# dos-partes.net
KiCad netlist of a schematic drawn in EAGLE
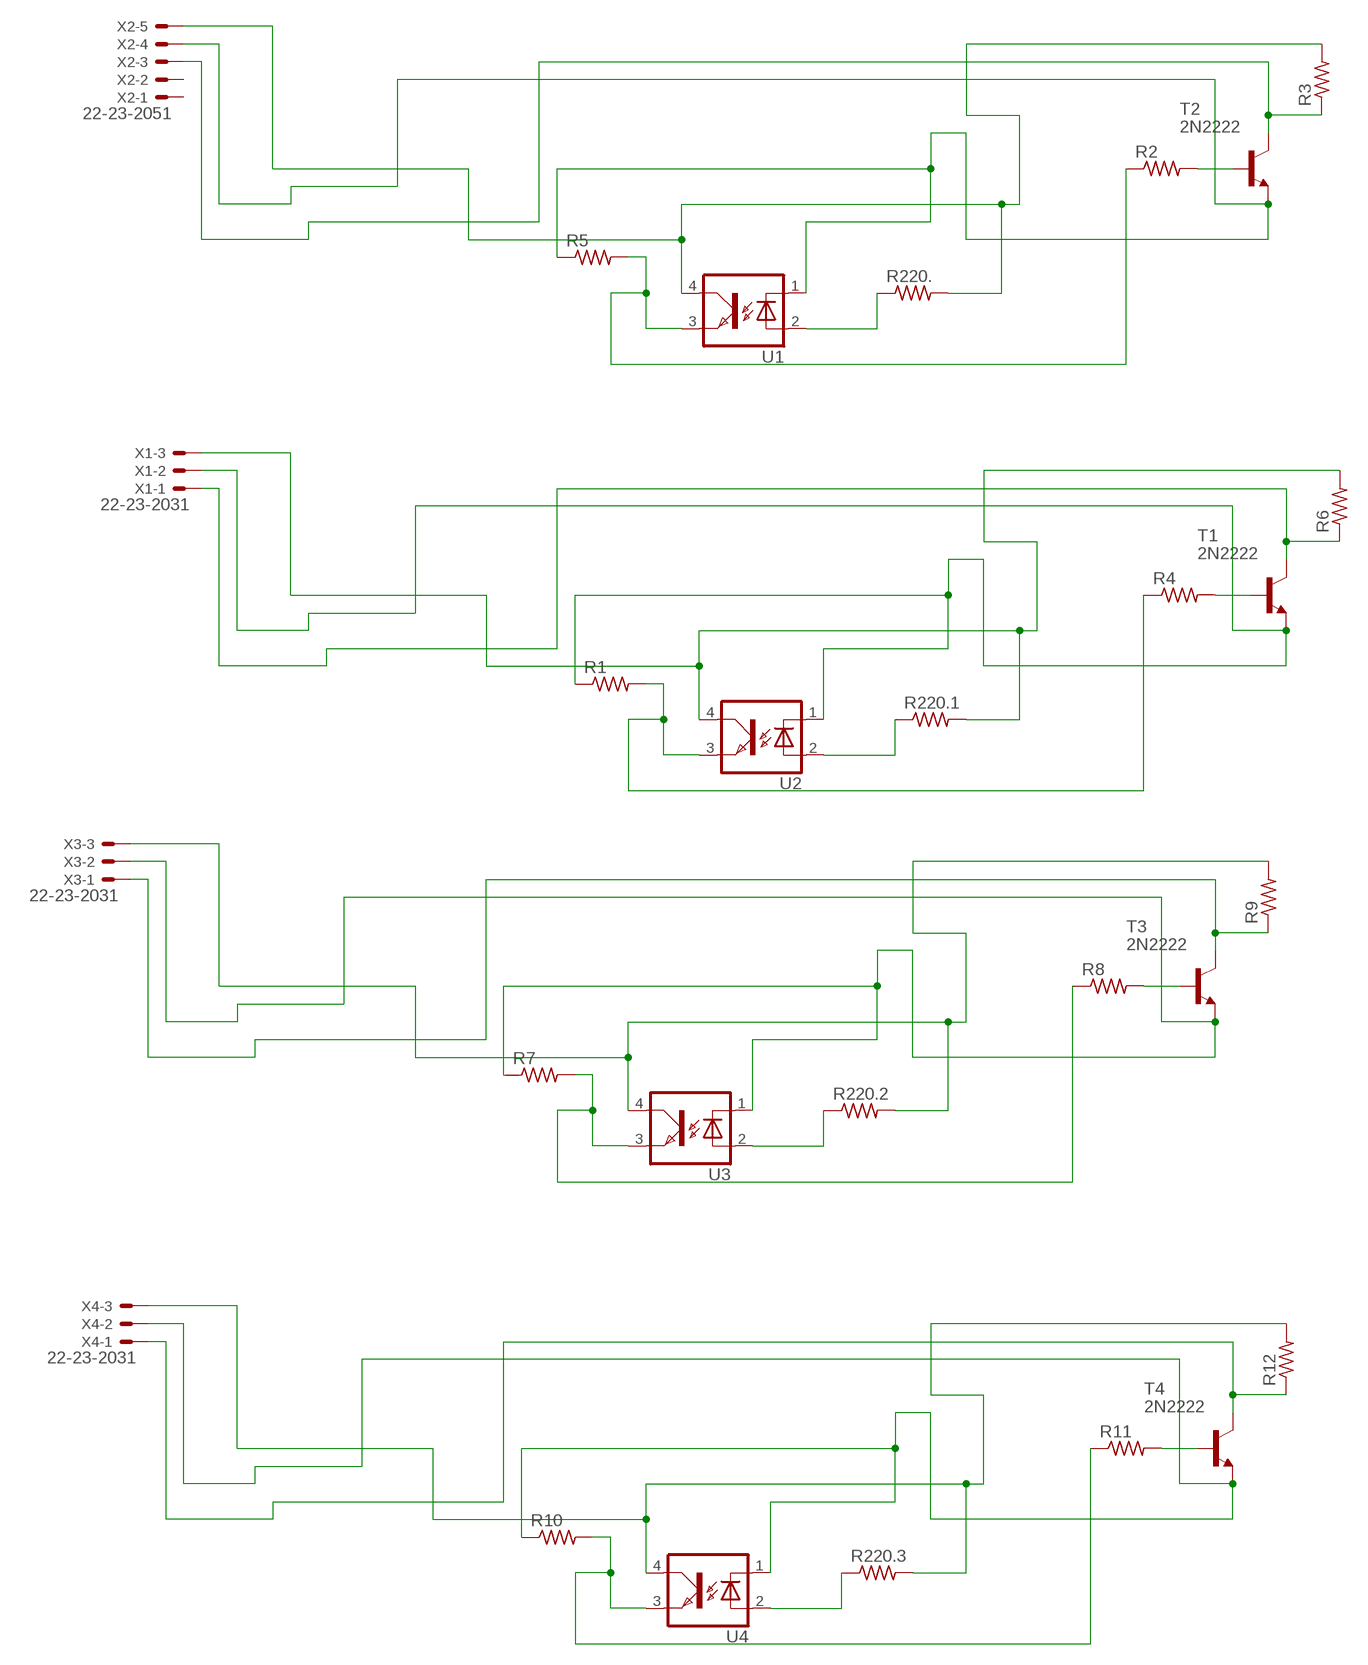
[diagram p0: schematic, sheet 1]

(export (version "E")
  (design (tool "Eeschema 10.0.6"))
  (components
    (comp (ref "R1")
      (value "R-US_0204/7")
      (footprint "eagle-import:0204_7")
      (libsource (lib "eagle-import") (part "R-US_0204/7"))
    )
    (comp (ref "R2")
      (value "R-US_0204/7")
      (footprint "eagle-import:0204_7")
      (libsource (lib "eagle-import") (part "R-US_0204/7"))
    )
    (comp (ref "R3")
      (value "R-US_0204/7")
      (footprint "eagle-import:0204_7")
      (libsource (lib "eagle-import") (part "R-US_0204/7"))
    )
    (comp (ref "R4")
      (value "R-US_0204/7")
      (footprint "eagle-import:0204_7")
      (libsource (lib "eagle-import") (part "R-US_0204/7"))
    )
    (comp (ref "R5")
      (value "R-US_0204/7")
      (footprint "eagle-import:0204_7")
      (libsource (lib "eagle-import") (part "R-US_0204/7"))
    )
    (comp (ref "R6")
      (value "R-US_0204/7")
      (footprint "eagle-import:0204_7")
      (libsource (lib "eagle-import") (part "R-US_0204/7"))
    )
    (comp (ref "R7")
      (value "R-US_0204/7")
      (footprint "eagle-import:0204_7")
      (libsource (lib "eagle-import") (part "R-US_0204/7"))
    )
    (comp (ref "R8")
      (value "R-US_0204/7")
      (footprint "eagle-import:0204_7")
      (libsource (lib "eagle-import") (part "R-US_0204/7"))
    )
    (comp (ref "R9")
      (value "R-US_0204/7")
      (footprint "eagle-import:0204_7")
      (libsource (lib "eagle-import") (part "R-US_0204/7"))
    )
    (comp (ref "R10")
      (value "R-US_0204/7")
      (footprint "eagle-import:0204_7")
      (libsource (lib "eagle-import") (part "R-US_0204/7"))
    )
    (comp (ref "R11")
      (value "R-US_0204/7")
      (footprint "eagle-import:0204_7")
      (libsource (lib "eagle-import") (part "R-US_0204/7"))
    )
    (comp (ref "R12")
      (value "R-US_0204/7")
      (footprint "eagle-import:0204_7")
      (libsource (lib "eagle-import") (part "R-US_0204/7"))
    )
    (comp (ref "R220.")
      (value "R-US_0204/7")
      (footprint "eagle-import:0204_7")
      (libsource (lib "eagle-import") (part "R-US_0204/7"))
    )
    (comp (ref "R220.1")
      (value "R-US_0204/7")
      (footprint "eagle-import:0204_7")
      (libsource (lib "eagle-import") (part "R-US_0204/7"))
    )
    (comp (ref "R220.2")
      (value "R-US_0204/7")
      (footprint "eagle-import:0204_7")
      (libsource (lib "eagle-import") (part "R-US_0204/7"))
    )
    (comp (ref "R220.3")
      (value "R-US_0204/7")
      (footprint "eagle-import:0204_7")
      (libsource (lib "eagle-import") (part "R-US_0204/7"))
    )
    (comp (ref "T1")
      (value "2N2222")
      (footprint "eagle-import:TO18")
      (libsource (lib "eagle-import") (part "2N2222"))
    )
    (comp (ref "T2")
      (value "2N2222")
      (footprint "eagle-import:TO18")
      (libsource (lib "eagle-import") (part "2N2222"))
    )
    (comp (ref "T3")
      (value "2N2222")
      (footprint "eagle-import:TO18")
      (libsource (lib "eagle-import") (part "2N2222"))
    )
    (comp (ref "T4")
      (value "2N2222")
      (footprint "eagle-import:TO18")
      (libsource (lib "eagle-import") (part "2N2222"))
    )
    (comp (ref "U1")
      (value "CNY70")
      (footprint "eagle-import:CNY70")
      (libsource (lib "eagle-import") (part "CNY70"))
    )
    (comp (ref "U2")
      (value "CNY70")
      (footprint "eagle-import:CNY70")
      (libsource (lib "eagle-import") (part "CNY70"))
    )
    (comp (ref "U3")
      (value "CNY70")
      (footprint "eagle-import:CNY70")
      (libsource (lib "eagle-import") (part "CNY70"))
    )
    (comp (ref "U4")
      (value "CNY70")
      (footprint "eagle-import:CNY70")
      (libsource (lib "eagle-import") (part "CNY70"))
    )
    (comp (ref "X1")
      (value "22-23-2031")
      (footprint "eagle-import:22-23-2031")
      (fields (field (name "MF") "MOLEX"))
      (libsource (lib "eagle-import") (part "22-23-2031"))
    )
    (comp (ref "X2")
      (value "22-23-2051")
      (footprint "eagle-import:22-23-2051")
      (fields (field (name "MF") "MOLEX"))
      (libsource (lib "eagle-import") (part "22-23-2051"))
    )
    (comp (ref "X3")
      (value "22-23-2031")
      (footprint "eagle-import:22-23-2031")
      (fields (field (name "MF") "MOLEX"))
      (libsource (lib "eagle-import") (part "22-23-2031"))
    )
    (comp (ref "X4")
      (value "22-23-2031")
      (footprint "eagle-import:22-23-2031")
      (fields (field (name "MF") "MOLEX"))
      (libsource (lib "eagle-import") (part "22-23-2031"))
    )
  )
  (nets
    (net (code "1") (name "Net-(R1-Pad2)") (class "Default")
      (node (ref "R1") (pin "2") (pinfunction "2_2") (pintype "passive"))
      (node (ref "R4") (pin "1") (pinfunction "1_1") (pintype "passive"))
      (node (ref "U2") (pin "3") (pinfunction "3_3") (pintype "passive"))
    )
    (net (code "2") (name "Net-(R2-Pad1)") (class "Default")
      (node (ref "R2") (pin "1") (pinfunction "1_1") (pintype "passive"))
      (node (ref "R5") (pin "2") (pinfunction "2_2") (pintype "passive"))
      (node (ref "U1") (pin "3") (pinfunction "3_3") (pintype "passive"))
    )
    (net (code "3") (name "Net-(R7-Pad2)") (class "Default")
      (node (ref "R7") (pin "2") (pinfunction "2_2") (pintype "passive"))
      (node (ref "R8") (pin "1") (pinfunction "1_1") (pintype "passive"))
      (node (ref "U3") (pin "3") (pinfunction "3_3") (pintype "passive"))
    )
    (net (code "4") (name "Net-(R10-Pad2)") (class "Default")
      (node (ref "R10") (pin "2") (pinfunction "2_2") (pintype "passive"))
      (node (ref "R11") (pin "1") (pinfunction "1_1") (pintype "passive"))
      (node (ref "U4") (pin "3") (pinfunction "3_3") (pintype "passive"))
    )
    (net (code "5") (name "Net-(R220.-Pad1)") (class "Default")
      (node (ref "R220.") (pin "1") (pinfunction "1_1") (pintype "passive"))
      (node (ref "U1") (pin "2") (pinfunction "2_2") (pintype "passive"))
    )
    (net (code "6") (name "Net-(R220.1-Pad1)") (class "Default")
      (node (ref "R220.1") (pin "1") (pinfunction "1_1") (pintype "passive"))
      (node (ref "U2") (pin "2") (pinfunction "2_2") (pintype "passive"))
    )
    (net (code "7") (name "Net-(R220.2-Pad1)") (class "Default")
      (node (ref "R220.2") (pin "1") (pinfunction "1_1") (pintype "passive"))
      (node (ref "U3") (pin "2") (pinfunction "2_2") (pintype "passive"))
    )
    (net (code "8") (name "Net-(R220.3-Pad1)") (class "Default")
      (node (ref "R220.3") (pin "1") (pinfunction "1_1") (pintype "passive"))
      (node (ref "U4") (pin "2") (pinfunction "2_2") (pintype "passive"))
    )
    (net (code "9") (name "Net-(T1-B)") (class "Default")
      (node (ref "R4") (pin "2") (pinfunction "2_2") (pintype "passive"))
      (node (ref "T1") (pin "2") (pinfunction "B_2") (pintype "passive"))
    )
    (net (code "10") (name "Net-(T1-C)") (class "Default")
      (node (ref "R6") (pin "1") (pinfunction "1_1") (pintype "passive"))
      (node (ref "T1") (pin "3") (pinfunction "C_3") (pintype "passive"))
      (node (ref "X1") (pin "1") (pinfunction "S_1") (pintype "passive"))
    )
    (net (code "11") (name "Net-(T1-E)") (class "Default")
      (node (ref "R1") (pin "1") (pinfunction "1_1") (pintype "passive"))
      (node (ref "T1") (pin "1") (pinfunction "E_1") (pintype "passive"))
      (node (ref "U2") (pin "1") (pinfunction "1_1") (pintype "passive"))
      (node (ref "X1") (pin "2") (pinfunction "S_2") (pintype "passive"))
    )
    (net (code "12") (name "Net-(T2-B)") (class "Default")
      (node (ref "R2") (pin "2") (pinfunction "2_2") (pintype "passive"))
      (node (ref "T2") (pin "2") (pinfunction "B_2") (pintype "passive"))
    )
    (net (code "13") (name "Net-(T2-C)") (class "Default")
      (node (ref "R3") (pin "1") (pinfunction "1_1") (pintype "passive"))
      (node (ref "T2") (pin "3") (pinfunction "C_3") (pintype "passive"))
      (node (ref "X2") (pin "3") (pinfunction "S_3") (pintype "passive"))
    )
    (net (code "14") (name "Net-(T2-E)") (class "Default")
      (node (ref "R5") (pin "1") (pinfunction "1_1") (pintype "passive"))
      (node (ref "T2") (pin "1") (pinfunction "E_1") (pintype "passive"))
      (node (ref "U1") (pin "1") (pinfunction "1_1") (pintype "passive"))
      (node (ref "X2") (pin "4") (pinfunction "S_4") (pintype "passive"))
    )
    (net (code "15") (name "Net-(T3-B)") (class "Default")
      (node (ref "R8") (pin "2") (pinfunction "2_2") (pintype "passive"))
      (node (ref "T3") (pin "2") (pinfunction "B_2") (pintype "passive"))
    )
    (net (code "16") (name "Net-(T3-C)") (class "Default")
      (node (ref "R9") (pin "1") (pinfunction "1_1") (pintype "passive"))
      (node (ref "T3") (pin "3") (pinfunction "C_3") (pintype "passive"))
      (node (ref "X3") (pin "1") (pinfunction "S_1") (pintype "passive"))
    )
    (net (code "17") (name "Net-(T3-E)") (class "Default")
      (node (ref "R7") (pin "1") (pinfunction "1_1") (pintype "passive"))
      (node (ref "T3") (pin "1") (pinfunction "E_1") (pintype "passive"))
      (node (ref "U3") (pin "1") (pinfunction "1_1") (pintype "passive"))
      (node (ref "X3") (pin "2") (pinfunction "S_2") (pintype "passive"))
    )
    (net (code "18") (name "Net-(T4-B)") (class "Default")
      (node (ref "R11") (pin "2") (pinfunction "2_2") (pintype "passive"))
      (node (ref "T4") (pin "2") (pinfunction "B_2") (pintype "passive"))
    )
    (net (code "19") (name "Net-(T4-C)") (class "Default")
      (node (ref "R12") (pin "1") (pinfunction "1_1") (pintype "passive"))
      (node (ref "T4") (pin "3") (pinfunction "C_3") (pintype "passive"))
      (node (ref "X4") (pin "1") (pinfunction "S_1") (pintype "passive"))
    )
    (net (code "20") (name "Net-(T4-E)") (class "Default")
      (node (ref "R10") (pin "1") (pinfunction "1_1") (pintype "passive"))
      (node (ref "T4") (pin "1") (pinfunction "E_1") (pintype "passive"))
      (node (ref "U4") (pin "1") (pinfunction "1_1") (pintype "passive"))
      (node (ref "X4") (pin "2") (pinfunction "S_2") (pintype "passive"))
    )
    (net (code "21") (name "Net-(X1C-S)") (class "Default")
      (node (ref "R220.1") (pin "2") (pinfunction "2_2") (pintype "passive"))
      (node (ref "R6") (pin "2") (pinfunction "2_2") (pintype "passive"))
      (node (ref "U2") (pin "4") (pinfunction "4_4") (pintype "passive"))
      (node (ref "X1") (pin "3") (pinfunction "S_3") (pintype "passive"))
    )
    (net (code "22") (name "Net-(X2E-S)") (class "Default")
      (node (ref "R220.") (pin "2") (pinfunction "2_2") (pintype "passive"))
      (node (ref "R3") (pin "2") (pinfunction "2_2") (pintype "passive"))
      (node (ref "U1") (pin "4") (pinfunction "4_4") (pintype "passive"))
      (node (ref "X2") (pin "5") (pinfunction "S_5") (pintype "passive"))
    )
    (net (code "23") (name "Net-(X3C-S)") (class "Default")
      (node (ref "R220.2") (pin "2") (pinfunction "2_2") (pintype "passive"))
      (node (ref "R9") (pin "2") (pinfunction "2_2") (pintype "passive"))
      (node (ref "U3") (pin "4") (pinfunction "4_4") (pintype "passive"))
      (node (ref "X3") (pin "3") (pinfunction "S_3") (pintype "passive"))
    )
    (net (code "24") (name "Net-(X4C-S)") (class "Default")
      (node (ref "R12") (pin "2") (pinfunction "2_2") (pintype "passive"))
      (node (ref "R220.3") (pin "2") (pinfunction "2_2") (pintype "passive"))
      (node (ref "U4") (pin "4") (pinfunction "4_4") (pintype "passive"))
      (node (ref "X4") (pin "3") (pinfunction "S_3") (pintype "passive"))
    )
    (net (code "25") (name "unconnected-(X2A-S-Pad1)") (class "Default")
      (node (ref "X2") (pin "1") (pinfunction "S_1") (pintype "passive"))
    )
    (net (code "26") (name "unconnected-(X2B-S-Pad2)") (class "Default")
      (node (ref "X2") (pin "2") (pinfunction "S_2") (pintype "passive"))
    )
  )
)
